# main.net
KiCad netlist of a schematic drawn in Altium Designer
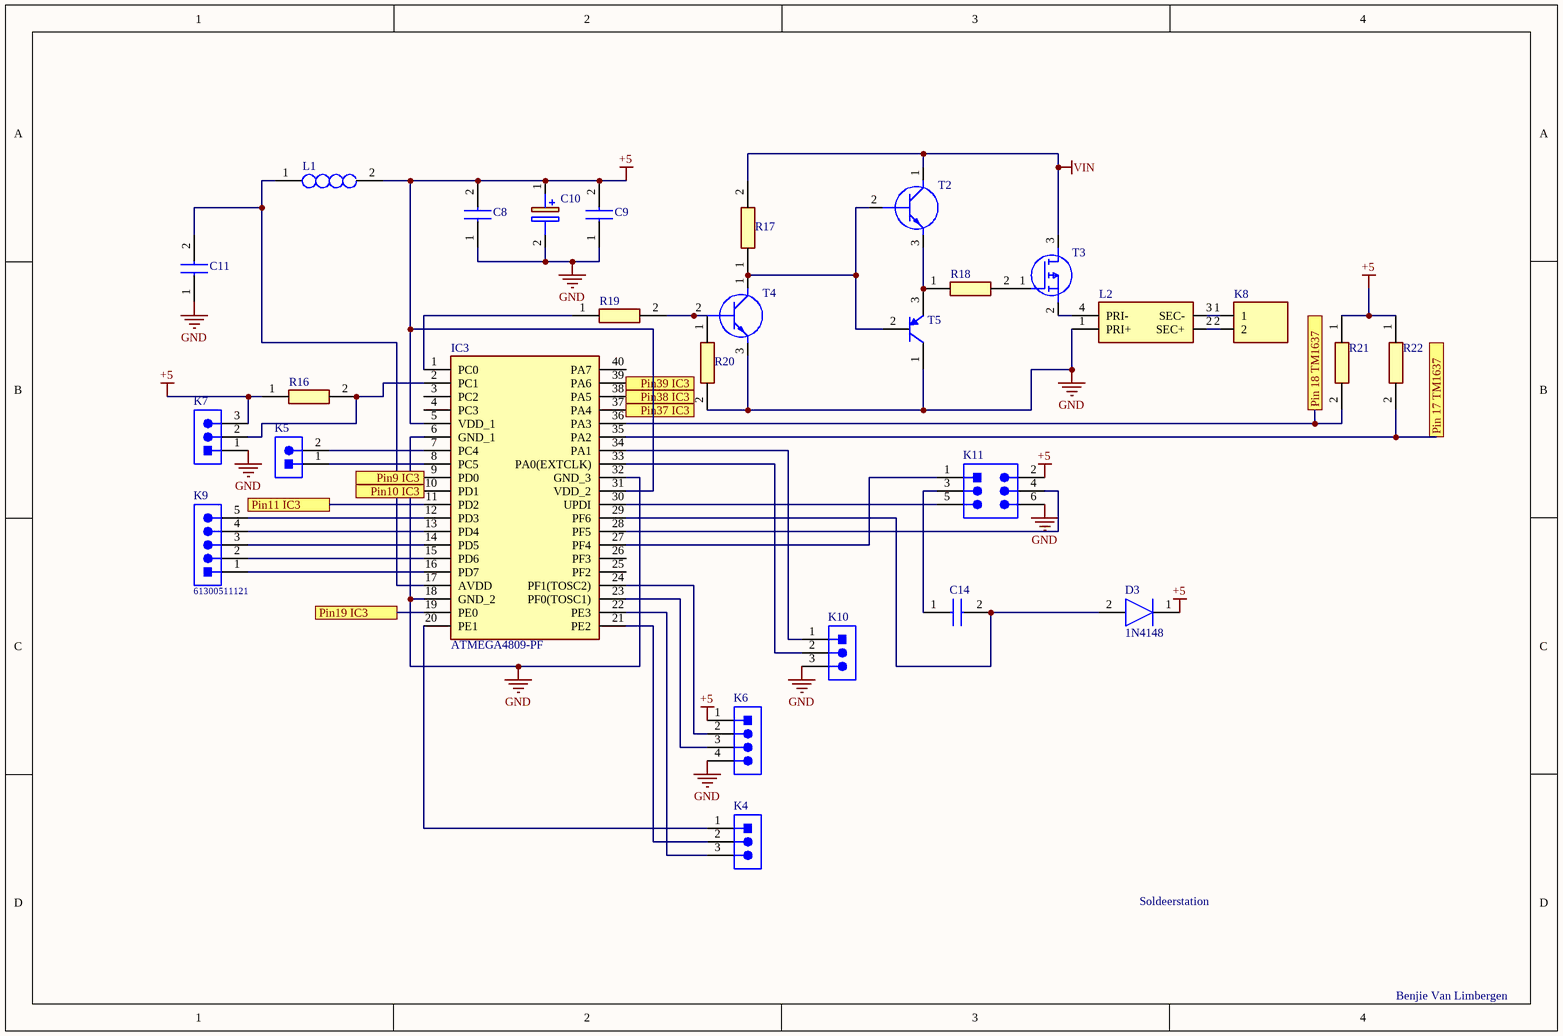
[diagram p0: main.SchDoc]

(export (version "E")
  (design (tool "Eeschema 10.0.6"))
  (components
    (comp (ref "C8")
      (value "885012207098")
      (footprint "SamacSys:CAPC2012X90N")
      (description "Capacitor, C3,C8,C9,C11,C14")
      (fields (field (name "MOUSER2 PART NUMBER") "710-885012207098"))
      (libsource (lib "*") (part "885012207098"))
    )
    (comp (ref "C9")
      (value "885012207098")
      (footprint "SamacSys:CAPC2012X90N")
      (description "Capacitor, C3,C8,C9,C11,C14")
      (fields (field (name "MOUSER2 PART NUMBER") "710-885012207098"))
      (libsource (lib "*") (part "885012207098"))
    )
    (comp (ref "C10")
      (value "860240672002")
      (footprint "SamacSys:CAPPRD200W52D500H1250")
      (description "Capacitor Polarised c10")
      (libsource (lib "*") (part "860240672002"))
    )
    (comp (ref "C11")
      (value "885012207098")
      (footprint "SamacSys:CAPC2012X90N")
      (description "Capacitor, C3,C8,C9,C11,C14")
      (fields (field (name "MOUSER2 PART NUMBER") "710-885012207098"))
      (libsource (lib "*") (part "885012207098"))
    )
    (comp (ref "C14")
      (value "885012207092")
      (footprint "SamacSys:CAPC2012X90N")
      (description "Capacitor c14 100n")
      (libsource (lib "*") (part "885012207092"))
    )
    (comp (ref "D3")
      (value "1N4148")
      (footprint "SamacSys:DIOAD1165W56L425D185")
      (description "Diode D3")
      (libsource (lib "*") (part "1N4148"))
    )
    (comp (ref "IC3")
      (value "ATMEGA4809-PF")
      (footprint "SamacSys:DIP1543W58P254L5175H635Q40N")
      (description "Integrated Circuit")
      (fields (field (name "MOUSER2 PART NUMBER") "556-ATMEGA4809-PF"))
      (libsource (lib "*") (part "ATMEGA4809-PF"))
    )
    (comp (ref "K4")
      (value "61300311121")
      (footprint "HDR1X3")
      (description "WR-PHD Pin Header, THT, pitch 2.54mm, Single Row, Vertical, 3p")
      (fields (field (name "MANUFACTURER") "Wurth Elektronik"))
      (libsource (lib "") (part "61300311121_1"))
    )
    (comp (ref "K5")
      (value "61300211121")
      (footprint "HDR1X2")
      (description "WR-PHD Pin Header, THT, pitch 2.54mm, Single Row, Vertical, 2p")
      (fields (field (name "MANUFACTURER") "Wurth Elektronik"))
      (libsource (lib "WR-PHD_Pin Header") (part "61300211121"))
    )
    (comp (ref "K6")
      (value "61000418221")
      (footprint "HDR1X4")
      (description "4p Header K6")
      (fields (field (name "MANUFACTURER") "Wurth Elektronik"))
      (libsource (lib "WR-PHD_Pin Header") (part "61000418221"))
    )
    (comp (ref "K7")
      (value "61300311121")
      (footprint "HDR1X3")
      (description "WR-PHD Pin Header, THT, pitch 2.54mm, Single Row, Vertical, 3p")
      (fields (field (name "MANUFACTURER") "Wurth Elektronik"))
      (libsource (lib "WR-PHD_Pin Header") (part "61300311121"))
    )
    (comp (ref "K8")
      (value "691214110002")
      (footprint "SamacSys:691214110002")
      (description "Connector")
      (libsource (lib "*") (part "691214110002"))
    )
    (comp (ref "K9")
      (value "61300511121")
      (footprint "HDR1X5")
      (description "5P Header k9")
      (fields (field (name "MANUFACTURER") "Wurth Elektronik"))
      (libsource (lib "WR-PHD_Pin Header") (part "61300511121"))
    )
    (comp (ref "K10")
      (value "61300311121")
      (footprint "HDR1X3")
      (description "3p header K10")
      (fields (field (name "MANUFACTURER") "Wurth Elektronik"))
      (libsource (lib "") (part "61300311121_1"))
    )
    (comp (ref "K11")
      (value "61000621121")
      (footprint "HDR2X3")
      (description "WR-PHD Pin Header, SMT, pitch 2.54mm, Dual Row, Vertical, 6p")
      (fields (field (name "MANUFACTURER") "Wurth Elektronik"))
      (libsource (lib "WR-PHD_Pin Header") (part "61000621121"))
    )
    (comp (ref "L1")
      (value "744711003")
      (footprint "SamacSys:744711003")
      (description "Inductor, Smoorspoel 10uH")
      (libsource (lib "*") (part "744711003"))
    )
    (comp (ref "L2")
      (value "CM2545X171B-10")
      (footprint "SamacSys:CM2545X171B10")
      (description "Transformer")
      (libsource (lib "*") (part "CM2545X171B-10"))
    )
    (comp (ref "R16")
      (value "C")
      (footprint "SamacSys:RESC2012X60N")
      (description "Resistor R1-22\r\n4k7")
      (fields
        (field (name "MOUSER2 PART NUMBER") "71-CRCW08051M00JNEAC")
        (field (name "MANUFACTURER_PART_NUMBER") "CRCW08051M00JNEAC")
      )
      (libsource (lib "") (part "CRCW08051M00JNEAC_2"))
    )
    (comp (ref "R17")
      (value "smd")
      (footprint "SamacSys:RESC2012X60N")
      (description "4k7")
      (fields
        (field (name "MOUSER2 PART NUMBER") "71-CRCW08051M00JNEAC")
        (field (name "MANUFACTURER_PART_NUMBER") "CRCW08051M00JNEAC")
      )
      (libsource (lib "") (part "CRCW08051M00JNEAC_1"))
    )
    (comp (ref "R18")
      (value "smd")
      (footprint "SamacSys:RESC2012X60N")
      (description "100k")
      (fields
        (field (name "MOUSER2 PART NUMBER") "71-CRCW08051M00JNEAC")
        (field (name "MANUFACTURER_PART_NUMBER") "CRCW08051M00JNEAC")
      )
      (libsource (lib "") (part "CRCW08051M00JNEAC_2"))
    )
    (comp (ref "R19")
      (value "smd")
      (footprint "SamacSys:RESC2012X60N")
      (description "10k")
      (fields
        (field (name "MOUSER2 PART NUMBER") "71-CRCW08051M00JNEAC")
        (field (name "MANUFACTURER_PART_NUMBER") "CRCW08051M00JNEAC")
      )
      (libsource (lib "") (part "CRCW08051M00JNEAC_2"))
    )
    (comp (ref "R20")
      (value "smd")
      (footprint "SamacSys:RESC2012X60N")
      (description "Resistor R1-22\r\n4k7")
      (fields
        (field (name "MOUSER2 PART NUMBER") "71-CRCW08051M00JNEAC")
        (field (name "MANUFACTURER_PART_NUMBER") "CRCW08051M00JNEAC")
      )
      (libsource (lib "SamacSys") (part "CRCW08051M00JNEAC"))
    )
    (comp (ref "R21")
      (value "CRCW08051M00JNEAC")
      (footprint "SamacSys:RESC2012X60N")
      (description "Resistor R1-22")
      (fields (field (name "MOUSER2 PART NUMBER") "71-CRCW08051M00JNEAC"))
      (libsource (lib "SamacSys") (part "CRCW08051M00JNEAC"))
    )
    (comp (ref "R22")
      (value "CRCW08051M00JNEAC")
      (footprint "SamacSys:RESC2012X60N")
      (description "Resistor R1-22")
      (fields (field (name "MOUSER2 PART NUMBER") "71-CRCW08051M00JNEAC"))
      (libsource (lib "SamacSys") (part "CRCW08051M00JNEAC"))
    )
    (comp (ref "T2")
      (value "BC547CBU")
      (footprint "SamacSys:BC547CBU")
      (description "Transistor BJT NPN")
      (libsource (lib "*") (part "BC547CBU"))
    )
    (comp (ref "T3")
      (value "IRF9Z34NPBF")
      (footprint "SamacSys:TO254P469X1042X1967-3P")
      (description "MOSFET (P-Channel)")
      (fields (field (name "MOUSER2 PART NUMBER") "942-IRF9Z34NPBF"))
      (libsource (lib "*") (part "IRF9Z34NPBF"))
    )
    (comp (ref "T4")
      (value "BC547CBU")
      (footprint "SamacSys:BC547CBU")
      (description "Transistor BJT NPN")
      (libsource (lib "*") (part "BC547CBU"))
    )
    (comp (ref "T5")
      (value "BC557CG")
      (footprint "ONSC-TO-92-3-29-11")
      (description "Amplifier Transistor, PNP Silicon, 3-Pin TO-92, Pb-Free, Bulk Box")
      (fields (field (name "MANUFACTURER") "On Semiconductor"))
      (libsource (lib "Altium Content Vault") (part "ONSC-PNP-C1B2E3-3"))
    )
  )
  (nets
    (net (code "1") (name "+5") (class "Default")
      (node (ref "C10") (pin "1") (pinfunction "+_1") (pintype "passive"))
      (node (ref "C8") (pin "2") (pinfunction "2_2") (pintype "passive"))
      (node (ref "C9") (pin "2") (pinfunction "2_2") (pintype "passive"))
      (node (ref "D3") (pin "1") (pinfunction "K_1") (pintype "passive"))
      (node (ref "IC3") (pin "31") (pinfunction "VDD_2_31") (pintype "passive"))
      (node (ref "IC3") (pin "5") (pinfunction "VDD_1_5") (pintype "passive"))
      (node (ref "K11") (pin "2") (pinfunction "2_2") (pintype "passive"))
      (node (ref "K6") (pin "1") (pinfunction "1_1") (pintype "passive"))
      (node (ref "K7") (pin "3") (pinfunction "3_3") (pintype "passive"))
      (node (ref "L1") (pin "2") (pinfunction "2_2") (pintype "passive"))
      (node (ref "R16") (pin "1") (pinfunction "1_1") (pintype "passive"))
      (node (ref "R21") (pin "1") (pinfunction "1_1") (pintype "passive"))
      (node (ref "R22") (pin "1") (pinfunction "1_1") (pintype "passive"))
    )
    (net (code "2") (name "/Pin 17 TM1637") (class "Default")
      (node (ref "IC3") (pin "35") (pinfunction "PA2_35") (pintype "passive"))
      (node (ref "R22") (pin "2") (pinfunction "2_2") (pintype "passive"))
    )
    (net (code "3") (name "/Pin 18 TM1637") (class "Default")
      (node (ref "IC3") (pin "36") (pinfunction "PA3_36") (pintype "passive"))
      (node (ref "R21") (pin "2") (pinfunction "2_2") (pintype "passive"))
    )
    (net (code "4") (name "/Pin9 IC3") (class "Default")
      (node (ref "IC3") (pin "9") (pinfunction "PD0_9") (pintype "passive"))
    )
    (net (code "5") (name "/Pin10 IC3") (class "Default")
      (node (ref "IC3") (pin "10") (pinfunction "PD1_10") (pintype "passive"))
    )
    (net (code "6") (name "/Pin11 IC3") (class "Default")
      (node (ref "IC3") (pin "11") (pinfunction "PD2_11") (pintype "passive"))
    )
    (net (code "7") (name "/Pin19 IC3") (class "Default")
      (node (ref "IC3") (pin "19") (pinfunction "PE0_19") (pintype "passive"))
    )
    (net (code "8") (name "/Pin37 IC3") (class "Default")
      (node (ref "IC3") (pin "37") (pinfunction "PA4_37") (pintype "passive"))
    )
    (net (code "9") (name "/Pin38 IC3") (class "Default")
      (node (ref "IC3") (pin "38") (pinfunction "PA5_38") (pintype "passive"))
    )
    (net (code "10") (name "/Pin39 IC3") (class "Default")
      (node (ref "IC3") (pin "39") (pinfunction "PA6_39") (pintype "passive"))
    )
    (net (code "11") (name "GND") (class "Default")
      (node (ref "C10") (pin "2") (pinfunction "-_2") (pintype "passive"))
      (node (ref "C11") (pin "1") (pinfunction "1_1") (pintype "passive"))
      (node (ref "C8") (pin "1") (pinfunction "1_1") (pintype "passive"))
      (node (ref "C9") (pin "1") (pinfunction "1_1") (pintype "passive"))
      (node (ref "IC3") (pin "18") (pinfunction "GND_2_18") (pintype "passive"))
      (node (ref "IC3") (pin "32") (pinfunction "GND_3_32") (pintype "passive"))
      (node (ref "IC3") (pin "6") (pinfunction "GND_1_6") (pintype "passive"))
      (node (ref "K10") (pin "3") (pinfunction "3_3") (pintype "passive"))
      (node (ref "K11") (pin "6") (pinfunction "6_6") (pintype "passive"))
      (node (ref "K6") (pin "4") (pinfunction "4_4") (pintype "passive"))
      (node (ref "K7") (pin "1") (pinfunction "1_1") (pintype "passive"))
      (node (ref "L2") (pin "1") (pinfunction "PRI+_1") (pintype "passive"))
      (node (ref "R20") (pin "2") (pinfunction "2_2") (pintype "passive"))
      (node (ref "T4") (pin "3") (pinfunction "E_3") (pintype "passive"))
      (node (ref "T5") (pin "1") (pinfunction "C_1") (pintype "passive"))
    )
    (net (code "12") (name "Net-(C14-Pad1)") (class "Default")
      (node (ref "C14") (pin "1") (pinfunction "1_1") (pintype "passive"))
      (node (ref "K11") (pin "3") (pinfunction "3_3") (pintype "passive"))
    )
    (net (code "13") (name "Net-(D3-A)") (class "Default")
      (node (ref "C14") (pin "2") (pinfunction "2_2") (pintype "passive"))
      (node (ref "D3") (pin "2") (pinfunction "A_2") (pintype "passive"))
      (node (ref "IC3") (pin "29") (pinfunction "PF6_29") (pintype "passive"))
    )
    (net (code "14") (name "Net-(IC3-AVDD)") (class "Default")
      (node (ref "C11") (pin "2") (pinfunction "2_2") (pintype "passive"))
      (node (ref "IC3") (pin "17") (pinfunction "AVDD_17") (pintype "passive"))
      (node (ref "L1") (pin "1") (pinfunction "1_1") (pintype "passive"))
    )
    (net (code "15") (name "Net-(IC3-PA0(EXTCLK))") (class "Default")
      (node (ref "IC3") (pin "33") (pinfunction "PA0(EXTCLK)_33") (pintype "passive"))
      (node (ref "K10") (pin "2") (pinfunction "2_2") (pintype "passive"))
    )
    (net (code "16") (name "Net-(IC3-PA1)") (class "Default")
      (node (ref "IC3") (pin "34") (pinfunction "PA1_34") (pintype "passive"))
      (node (ref "K10") (pin "1") (pinfunction "1_1") (pintype "passive"))
    )
    (net (code "17") (name "Net-(IC3-PC0)") (class "Default")
      (node (ref "IC3") (pin "1") (pinfunction "PC0_1") (pintype "passive"))
      (node (ref "R19") (pin "1") (pinfunction "1_1") (pintype "passive"))
    )
    (net (code "18") (name "Net-(IC3-PC1)") (class "Default")
      (node (ref "IC3") (pin "2") (pinfunction "PC1_2") (pintype "passive"))
      (node (ref "K7") (pin "2") (pinfunction "2_2") (pintype "passive"))
      (node (ref "R16") (pin "2") (pinfunction "2_2") (pintype "passive"))
    )
    (net (code "19") (name "Net-(IC3-PC4)") (class "Default")
      (node (ref "IC3") (pin "7") (pinfunction "PC4_7") (pintype "passive"))
      (node (ref "K5") (pin "2") (pinfunction "2_2") (pintype "passive"))
    )
    (net (code "20") (name "Net-(IC3-PC5)") (class "Default")
      (node (ref "IC3") (pin "8") (pinfunction "PC5_8") (pintype "passive"))
      (node (ref "K5") (pin "1") (pinfunction "1_1") (pintype "passive"))
    )
    (net (code "21") (name "Net-(IC3-PD3)") (class "Default")
      (node (ref "IC3") (pin "12") (pinfunction "PD3_12") (pintype "passive"))
      (node (ref "K9") (pin "5") (pinfunction "5_5") (pintype "passive"))
    )
    (net (code "22") (name "Net-(IC3-PD4)") (class "Default")
      (node (ref "IC3") (pin "13") (pinfunction "PD4_13") (pintype "passive"))
      (node (ref "K9") (pin "4") (pinfunction "4_4") (pintype "passive"))
    )
    (net (code "23") (name "Net-(IC3-PD5)") (class "Default")
      (node (ref "IC3") (pin "14") (pinfunction "PD5_14") (pintype "passive"))
      (node (ref "K9") (pin "3") (pinfunction "3_3") (pintype "passive"))
    )
    (net (code "24") (name "Net-(IC3-PD6)") (class "Default")
      (node (ref "IC3") (pin "15") (pinfunction "PD6_15") (pintype "passive"))
      (node (ref "K9") (pin "2") (pinfunction "2_2") (pintype "passive"))
    )
    (net (code "25") (name "Net-(IC3-PD7)") (class "Default")
      (node (ref "IC3") (pin "16") (pinfunction "PD7_16") (pintype "passive"))
      (node (ref "K9") (pin "1") (pinfunction "1_1") (pintype "passive"))
    )
    (net (code "26") (name "Net-(IC3-PE1)") (class "Default")
      (node (ref "IC3") (pin "20") (pinfunction "PE1_20") (pintype "passive"))
      (node (ref "K4") (pin "1") (pinfunction "1_1") (pintype "passive"))
    )
    (net (code "27") (name "Net-(IC3-PE2)") (class "Default")
      (node (ref "IC3") (pin "21") (pinfunction "PE2_21") (pintype "passive"))
      (node (ref "K4") (pin "2") (pinfunction "2_2") (pintype "passive"))
    )
    (net (code "28") (name "Net-(IC3-PE3)") (class "Default")
      (node (ref "IC3") (pin "22") (pinfunction "PE3_22") (pintype "passive"))
      (node (ref "K4") (pin "3") (pinfunction "3_3") (pintype "passive"))
    )
    (net (code "29") (name "Net-(IC3-PF0(TOSC1))") (class "Default")
      (node (ref "IC3") (pin "23") (pinfunction "PF0(TOSC1)_23") (pintype "passive"))
      (node (ref "K6") (pin "3") (pinfunction "3_3") (pintype "passive"))
    )
    (net (code "30") (name "Net-(IC3-PF1(TOSC2))") (class "Default")
      (node (ref "IC3") (pin "24") (pinfunction "PF1(TOSC2)_24") (pintype "passive"))
      (node (ref "K6") (pin "2") (pinfunction "2_2") (pintype "passive"))
    )
    (net (code "31") (name "Net-(IC3-PF4)") (class "Default")
      (node (ref "IC3") (pin "27") (pinfunction "PF4_27") (pintype "passive"))
      (node (ref "K11") (pin "1") (pinfunction "1_1") (pintype "passive"))
    )
    (net (code "32") (name "Net-(IC3-PF5)") (class "Default")
      (node (ref "IC3") (pin "28") (pinfunction "PF5_28") (pintype "passive"))
      (node (ref "K11") (pin "4") (pinfunction "4_4") (pintype "passive"))
    )
    (net (code "33") (name "Net-(IC3-UPDI)") (class "Default")
      (node (ref "IC3") (pin "30") (pinfunction "UPDI_30") (pintype "passive"))
      (node (ref "K11") (pin "5") (pinfunction "5_5") (pintype "passive"))
    )
    (net (code "34") (name "Net-(L2-PRI-)") (class "Default")
      (node (ref "L2") (pin "4") (pinfunction "PRI-_4") (pintype "passive"))
      (node (ref "T3") (pin "2") (pinfunction "S_2") (pintype "passive"))
    )
    (net (code "35") (name "Net-(L2-SEC+)") (class "Default")
      (node (ref "K8") (pin "2") (pinfunction "2_2") (pintype "passive"))
      (node (ref "L2") (pin "2") (pinfunction "SEC+_2") (pintype "passive"))
    )
    (net (code "36") (name "Net-(L2-SEC-)") (class "Default")
      (node (ref "K8") (pin "1") (pinfunction "1_1") (pintype "passive"))
      (node (ref "L2") (pin "3") (pinfunction "SEC-_3") (pintype "passive"))
    )
    (net (code "37") (name "Net-(T2-B)") (class "Default")
      (node (ref "R17") (pin "1") (pinfunction "1_1") (pintype "passive"))
      (node (ref "T2") (pin "2") (pinfunction "B_2") (pintype "passive"))
      (node (ref "T4") (pin "1") (pinfunction "C_1") (pintype "passive"))
      (node (ref "T5") (pin "2") (pinfunction "B_2") (pintype "passive"))
    )
    (net (code "38") (name "Net-(T2-E)") (class "Default")
      (node (ref "R18") (pin "1") (pinfunction "1_1") (pintype "passive"))
      (node (ref "T2") (pin "3") (pinfunction "E_3") (pintype "passive"))
      (node (ref "T5") (pin "3") (pinfunction "E_3") (pintype "passive"))
    )
    (net (code "39") (name "Net-(T3-G)") (class "Default")
      (node (ref "R18") (pin "2") (pinfunction "2_2") (pintype "passive"))
      (node (ref "T3") (pin "1") (pinfunction "G_1") (pintype "passive"))
    )
    (net (code "40") (name "Net-(T4-B)") (class "Default")
      (node (ref "R19") (pin "2") (pinfunction "2_2") (pintype "passive"))
      (node (ref "R20") (pin "1") (pinfunction "1_1") (pintype "passive"))
      (node (ref "T4") (pin "2") (pinfunction "B_2") (pintype "passive"))
    )
    (net (code "41") (name "VIN") (class "Default")
      (node (ref "R17") (pin "2") (pinfunction "2_2") (pintype "passive"))
      (node (ref "T2") (pin "1") (pinfunction "C_1") (pintype "passive"))
      (node (ref "T3") (pin "3") (pinfunction "D_3") (pintype "passive"))
    )
    (net (code "42") (name "unconnected-(IC3-PA7-Pad40)") (class "Default")
      (node (ref "IC3") (pin "40") (pinfunction "PA7_40") (pintype "passive"))
    )
    (net (code "43") (name "unconnected-(IC3-PC2-Pad3)") (class "Default")
      (node (ref "IC3") (pin "3") (pinfunction "PC2_3") (pintype "passive"))
    )
    (net (code "44") (name "unconnected-(IC3-PC3-Pad4)") (class "Default")
      (node (ref "IC3") (pin "4") (pinfunction "PC3_4") (pintype "passive"))
    )
    (net (code "45") (name "unconnected-(IC3-PF2-Pad25)") (class "Default")
      (node (ref "IC3") (pin "25") (pinfunction "PF2_25") (pintype "passive"))
    )
    (net (code "46") (name "unconnected-(IC3-PF3-Pad26)") (class "Default")
      (node (ref "IC3") (pin "26") (pinfunction "PF3_26") (pintype "passive"))
    )
  )
)
